# untitled.net
KiCad netlist of a schematic drawn in EAGLE
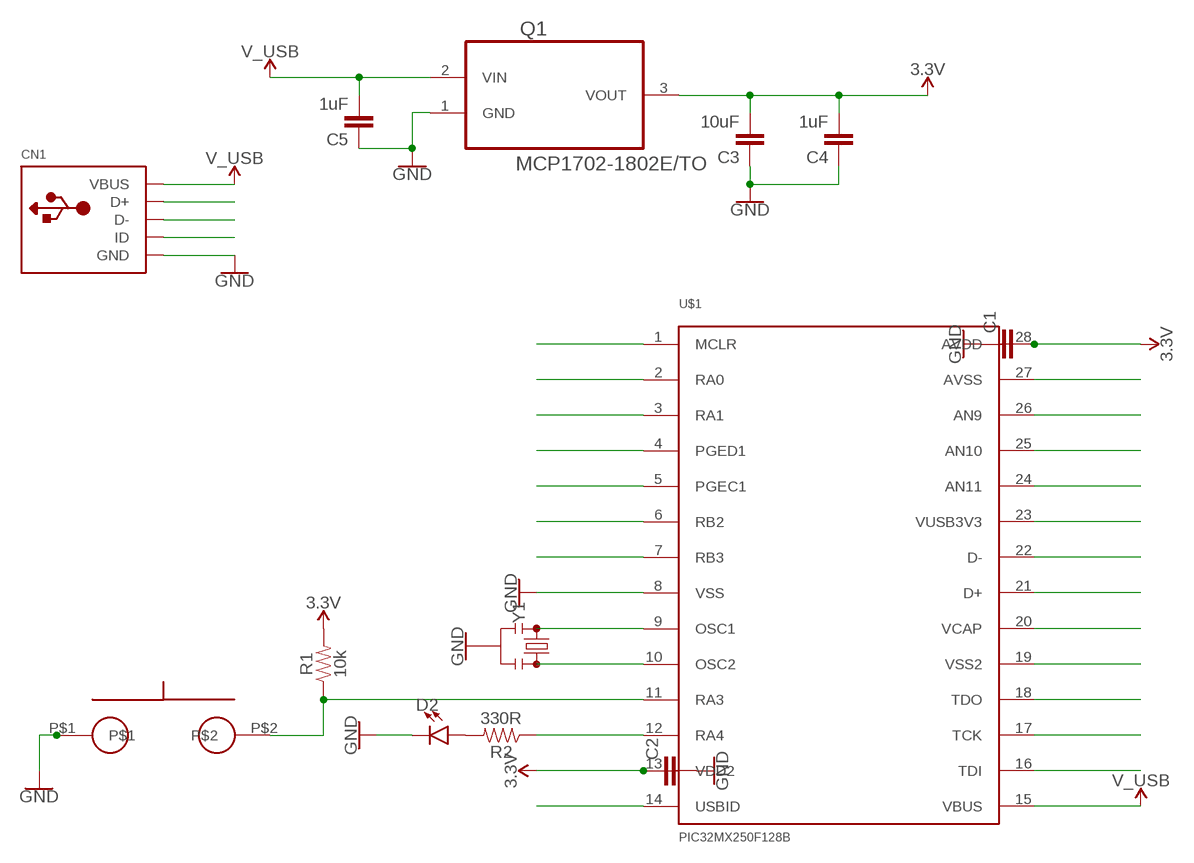
[diagram p0: schematic, sheet 1]

(export (version "E")
  (design (tool "Eeschema 10.0.6"))
  (components
    (comp (ref "C1")
      (value "CAPVERT_CAP")
      (footprint "eagle-import:PTH_VERT_CAP")
      (libsource (lib "eagle-import") (part "CAPVERT_CAP"))
    )
    (comp (ref "C2")
      (value "CAPVERT_CAP")
      (footprint "eagle-import:PTH_VERT_CAP")
      (libsource (lib "eagle-import") (part "CAPVERT_CAP"))
    )
    (comp (ref "C3")
      (value "10uF")
      (footprint "eagle-import:PTH_VERT_CAP")
      (libsource (lib "eagle-import") (part "CAPVERT_CAP"))
    )
    (comp (ref "C4")
      (value "1uF")
      (footprint "eagle-import:PTH_VERT_CAP")
      (libsource (lib "eagle-import") (part "CAPVERT_CAP"))
    )
    (comp (ref "C5")
      (value "1uF")
      (footprint "eagle-import:PTH_VERT_CAP")
      (libsource (lib "eagle-import") (part "CAPVERT_CAP"))
    )
    (comp (ref "CN1")
      (value "USBMINIB")
      (footprint "eagle-import:USB-MINIB")
      (libsource (lib "eagle-import") (part "USBMINIB"))
    )
    (comp (ref "D2")
      (value "LED3MM")
      (footprint "eagle-import:LED_3MM")
      (libsource (lib "eagle-import") (part "LED3MM"))
    )
    (comp (ref "Q1")
      (value "MCP1702-1802E/TO")
      (footprint "eagle-import:TO127P254X533-3")
      (libsource (lib "eagle-import") (part "MCP1702-1802E/TO"))
    )
    (comp (ref "R1")
      (value "10k")
      (footprint "eagle-import:AXIAL-0.3")
      (libsource (lib "eagle-import") (part "1KOHM-HORIZ-1/4W-5%"))
    )
    (comp (ref "R2")
      (value "330R")
      (footprint "eagle-import:AXIAL-0.3")
      (libsource (lib "eagle-import") (part "1KOHM-HORIZ-1/4W-5%"))
    )
    (comp (ref "U$1")
      (value "PIC32MX250F128B")
      (footprint "eagle-import:DIP28")
      (libsource (lib "eagle-import") (part "PIC32MX250F128B"))
    )
    (comp (ref "U$2")
      (value "EVQ11")
      (footprint "eagle-import:EVQ11")
      (libsource (lib "eagle-import") (part "EVQ11"))
    )
    (comp (ref "Y1")
      (value "RESONATORPTH-7.6X3.8")
      (footprint "eagle-import:RESONATOR-PTH-7.6X3.8")
      (libsource (lib "eagle-import") (part "RESONATORPTH-7.6X3.8"))
    )
  )
  (nets
    (net (code "1") (name "/D+") (class "Default")
      (node (ref "CN1") (pin "D+") (pinfunction "D+_D+") (pintype "bidirectional"))
      (node (ref "U$1") (pin "21") (pinfunction "D+_21") (pintype "bidirectional"))
    )
    (net (code "2") (name "/D-") (class "Default")
      (node (ref "CN1") (pin "D-") (pinfunction "D-_D-") (pintype "bidirectional"))
      (node (ref "U$1") (pin "22") (pinfunction "D-_22") (pintype "bidirectional"))
    )
    (net (code "3") (name "/ID") (class "Default")
      (node (ref "CN1") (pin "ID") (pinfunction "ID_ID") (pintype "bidirectional"))
      (node (ref "U$1") (pin "14") (pinfunction "USBID_14") (pintype "bidirectional"))
    )
    (net (code "4") (name "3.3V") (class "Default")
      (node (ref "C1") (pin "P$2") (pinfunction "2_P$2") (pintype "passive"))
      (node (ref "C2") (pin "P$1") (pinfunction "1_P$1") (pintype "passive"))
      (node (ref "C3") (pin "P$2") (pinfunction "2_P$2") (pintype "passive"))
      (node (ref "C4") (pin "P$2") (pinfunction "2_P$2") (pintype "passive"))
      (node (ref "Q1") (pin "3") (pinfunction "VOUT_3") (pintype "output"))
      (node (ref "R1") (pin "P$2") (pinfunction "2_P$2") (pintype "passive"))
      (node (ref "U$1") (pin "13") (pinfunction "VDD2_13") (pintype "bidirectional"))
      (node (ref "U$1") (pin "28") (pinfunction "AVDD_28") (pintype "bidirectional"))
    )
    (net (code "5") (name "GND") (class "Default")
      (node (ref "C1") (pin "P$1") (pinfunction "1_P$1") (pintype "passive"))
      (node (ref "C2") (pin "P$2") (pinfunction "2_P$2") (pintype "passive"))
      (node (ref "C3") (pin "P$1") (pinfunction "1_P$1") (pintype "passive"))
      (node (ref "C4") (pin "P$1") (pinfunction "1_P$1") (pintype "passive"))
      (node (ref "C5") (pin "P$1") (pinfunction "1_P$1") (pintype "passive"))
      (node (ref "CN1") (pin "GND") (pinfunction "GND_GND") (pintype "power_in"))
      (node (ref "D2") (pin "K") (pinfunction "C_K") (pintype "passive"))
      (node (ref "Q1") (pin "1") (pinfunction "GND_1") (pintype "passive"))
      (node (ref "U$1") (pin "8") (pinfunction "VSS_8") (pintype "bidirectional"))
      (node (ref "U$2") (pin "P$1") (pinfunction "P$1_P$1") (pintype "bidirectional"))
      (node (ref "Y1") (pin "2") (pinfunction "2_2") (pintype "passive"))
    )
    (net (code "6") (name "Net-(R1-1)") (class "Default")
      (node (ref "R1") (pin "P$1") (pinfunction "1_P$1") (pintype "passive"))
      (node (ref "U$1") (pin "11") (pinfunction "RA3_11") (pintype "bidirectional"))
      (node (ref "U$2") (pin "P$2") (pinfunction "P$2_P$2") (pintype "bidirectional"))
    )
    (net (code "7") (name "Net-(R2-1)") (class "Default")
      (node (ref "R2") (pin "P$1") (pinfunction "1_P$1") (pintype "passive"))
      (node (ref "U$1") (pin "12") (pinfunction "RA4_12") (pintype "bidirectional"))
    )
    (net (code "8") (name "Net-(R2-2)") (class "Default")
      (node (ref "D2") (pin "A") (pinfunction "A_A") (pintype "passive"))
      (node (ref "R2") (pin "P$2") (pinfunction "2_P$2") (pintype "passive"))
    )
    (net (code "9") (name "Net-(U$1-OSC1)") (class "Default")
      (node (ref "U$1") (pin "9") (pinfunction "OSC1_9") (pintype "bidirectional"))
      (node (ref "Y1") (pin "1") (pinfunction "1_1") (pintype "passive"))
    )
    (net (code "10") (name "Net-(U$1-OSC2)") (class "Default")
      (node (ref "U$1") (pin "10") (pinfunction "OSC2_10") (pintype "bidirectional"))
      (node (ref "Y1") (pin "3") (pinfunction "3_3") (pintype "passive"))
    )
    (net (code "11") (name "V_USB") (class "Default")
      (node (ref "C5") (pin "P$2") (pinfunction "2_P$2") (pintype "passive"))
      (node (ref "CN1") (pin "VBUS") (pinfunction "VBUS_VBUS") (pintype "power_in"))
      (node (ref "Q1") (pin "2") (pinfunction "VIN_2") (pintype "input"))
      (node (ref "U$1") (pin "15") (pinfunction "VBUS_15") (pintype "bidirectional"))
    )
    (net (code "12") (name "unconnected-(U$1-AN9-Pad26)") (class "Default")
      (node (ref "U$1") (pin "26") (pinfunction "AN9_26") (pintype "bidirectional"))
    )
    (net (code "13") (name "unconnected-(U$1-AN10-Pad25)") (class "Default")
      (node (ref "U$1") (pin "25") (pinfunction "AN10_25") (pintype "bidirectional"))
    )
    (net (code "14") (name "unconnected-(U$1-AN11-Pad24)") (class "Default")
      (node (ref "U$1") (pin "24") (pinfunction "AN11_24") (pintype "bidirectional"))
    )
    (net (code "15") (name "unconnected-(U$1-AVSS-Pad27)") (class "Default")
      (node (ref "U$1") (pin "27") (pinfunction "AVSS_27") (pintype "bidirectional"))
    )
    (net (code "16") (name "unconnected-(U$1-MCLR-Pad1)") (class "Default")
      (node (ref "U$1") (pin "1") (pinfunction "MCLR_1") (pintype "bidirectional"))
    )
    (net (code "17") (name "unconnected-(U$1-PGEC1-Pad5)") (class "Default")
      (node (ref "U$1") (pin "5") (pinfunction "PGEC1_5") (pintype "bidirectional"))
    )
    (net (code "18") (name "unconnected-(U$1-PGED1-Pad4)") (class "Default")
      (node (ref "U$1") (pin "4") (pinfunction "PGED1_4") (pintype "bidirectional"))
    )
    (net (code "19") (name "unconnected-(U$1-RA0-Pad2)") (class "Default")
      (node (ref "U$1") (pin "2") (pinfunction "RA0_2") (pintype "bidirectional"))
    )
    (net (code "20") (name "unconnected-(U$1-RA1-Pad3)") (class "Default")
      (node (ref "U$1") (pin "3") (pinfunction "RA1_3") (pintype "bidirectional"))
    )
    (net (code "21") (name "unconnected-(U$1-RB2-Pad6)") (class "Default")
      (node (ref "U$1") (pin "6") (pinfunction "RB2_6") (pintype "bidirectional"))
    )
    (net (code "22") (name "unconnected-(U$1-RB3-Pad7)") (class "Default")
      (node (ref "U$1") (pin "7") (pinfunction "RB3_7") (pintype "bidirectional"))
    )
    (net (code "23") (name "unconnected-(U$1-TCK-Pad17)") (class "Default")
      (node (ref "U$1") (pin "17") (pinfunction "TCK_17") (pintype "bidirectional"))
    )
    (net (code "24") (name "unconnected-(U$1-TDI-Pad16)") (class "Default")
      (node (ref "U$1") (pin "16") (pinfunction "TDI_16") (pintype "bidirectional"))
    )
    (net (code "25") (name "unconnected-(U$1-TDO-Pad18)") (class "Default")
      (node (ref "U$1") (pin "18") (pinfunction "TDO_18") (pintype "bidirectional"))
    )
    (net (code "26") (name "unconnected-(U$1-VCAP-Pad20)") (class "Default")
      (node (ref "U$1") (pin "20") (pinfunction "VCAP_20") (pintype "bidirectional"))
    )
    (net (code "27") (name "unconnected-(U$1-VSS2-Pad19)") (class "Default")
      (node (ref "U$1") (pin "19") (pinfunction "VSS2_19") (pintype "bidirectional"))
    )
    (net (code "28") (name "unconnected-(U$1-VUSB3V3-Pad23)") (class "Default")
      (node (ref "U$1") (pin "23") (pinfunction "VUSB3V3_23") (pintype "bidirectional"))
    )
  )
)
